# Input.net
KiCad netlist of a schematic drawn in Altium Designer
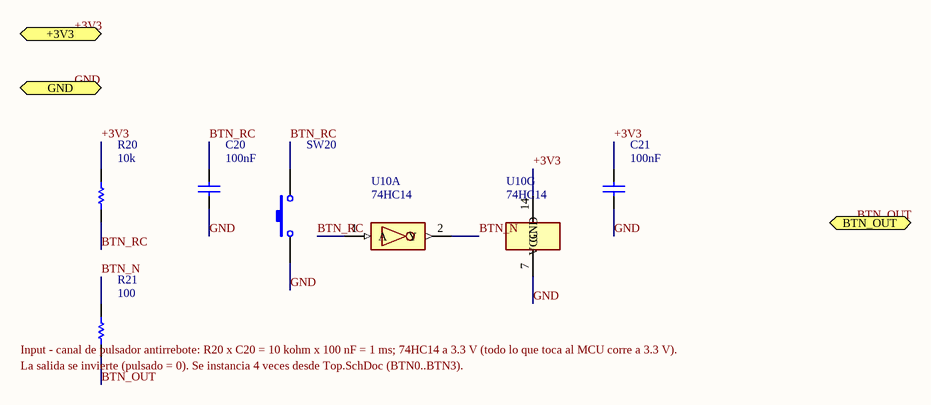
[diagram p0: Input.SchDoc]

(export (version "E")
  (design (tool "Eeschema 10.0.6"))
  (components
    (comp (ref "C20")
      (value "100nF")
      (description "Capacitor 100nF")
      (fields
        (field (name "MANUFACTURER") "KEMET")
        (field (name "MANUFACTURER PART NUMBER") "C0603C100nF")
        (field (name "PUBLISHER") "Altium Limited")
      )
      (libsource (lib "Miscellaneous Devices") (part "Cap"))
    )
    (comp (ref "C21")
      (value "100nF")
      (description "Capacitor 100nF")
      (fields
        (field (name "MANUFACTURER") "KEMET")
        (field (name "MANUFACTURER PART NUMBER") "C0603C100nF")
        (field (name "PUBLISHER") "Altium Limited")
      )
      (libsource (lib "Miscellaneous Devices") (part "Cap"))
    )
    (comp (ref "R20")
      (value "10k")
      (description "Resistor 10k 0603")
      (fields
        (field (name "MANUFACTURER") "Yageo")
        (field (name "MANUFACTURER PART NUMBER") "RC0603FR-0710K")
        (field (name "PUBLISHER") "Altium Limited")
      )
      (libsource (lib "Miscellaneous Devices") (part "Res1"))
    )
    (comp (ref "R21")
      (value "100")
      (description "Resistor 100 0603")
      (fields
        (field (name "MANUFACTURER") "Yageo")
        (field (name "MANUFACTURER PART NUMBER") "RC0603FR-07100")
        (field (name "PUBLISHER") "Altium Limited")
      )
      (libsource (lib "Miscellaneous Devices") (part "Res1"))
    )
    (comp (ref "SW20")
      (value "SW-PB")
      (description "Pulsador NA")
      (fields
        (field (name "MANUFACTURER") "Generic")
        (field (name "MANUFACTURER PART NUMBER") "Tactile 6x6")
        (field (name "PUBLISHER") "Altium Limited")
      )
      (libsource (lib "Miscellaneous Devices") (part "SW-PB"))
    )
    (comp (ref "U10")
      (value "74HC14")
      (footprint "DIP-14")
      (description "Hex Schmitt-trigger inverter 6 gates (A-F) + power part G (VCC=14, GND=7)")
      (fields
        (field (name "MANUFACTURER") "Texas Instruments")
        (field (name "MANUFACTURER PART NUMBER") "SN74HC14N")
      )
      (libsource (lib "*") (part "74HC14"))
    )
  )
  (nets
    (net (code "1") (name "/+3V3") (class "Default")
      (node (ref "C21") (pin "2") (pinfunction "2_2") (pintype "passive"))
      (node (ref "R20") (pin "2") (pinfunction "2_2") (pintype "passive"))
      (node (ref "U10") (pin "14") (pinfunction "VCC_14") (pintype "power_in"))
    )
    (net (code "2") (name "/BTN_N") (class "Default")
      (node (ref "R21") (pin "2") (pinfunction "2_2") (pintype "passive"))
      (node (ref "U10") (pin "2") (pinfunction "Y_2") (pintype "output"))
    )
    (net (code "3") (name "/BTN_OUT") (class "Default")
      (node (ref "R21") (pin "1") (pinfunction "1_1") (pintype "passive"))
    )
    (net (code "4") (name "/BTN_RC") (class "Default")
      (node (ref "C20") (pin "2") (pinfunction "2_2") (pintype "passive"))
      (node (ref "R20") (pin "1") (pinfunction "1_1") (pintype "passive"))
      (node (ref "SW20") (pin "2") (pinfunction "2_2") (pintype "passive"))
      (node (ref "U10") (pin "1") (pinfunction "A_1") (pintype "input"))
    )
    (net (code "5") (name "/GND") (class "Default")
      (node (ref "C20") (pin "1") (pinfunction "1_1") (pintype "passive"))
      (node (ref "C21") (pin "1") (pinfunction "1_1") (pintype "passive"))
      (node (ref "SW20") (pin "1") (pinfunction "1_1") (pintype "passive"))
      (node (ref "U10") (pin "7") (pinfunction "GND_7") (pintype "power_in"))
    )
  )
)
